# DevShield2_7_1.net
KiCad netlist of a schematic drawn in EAGLE
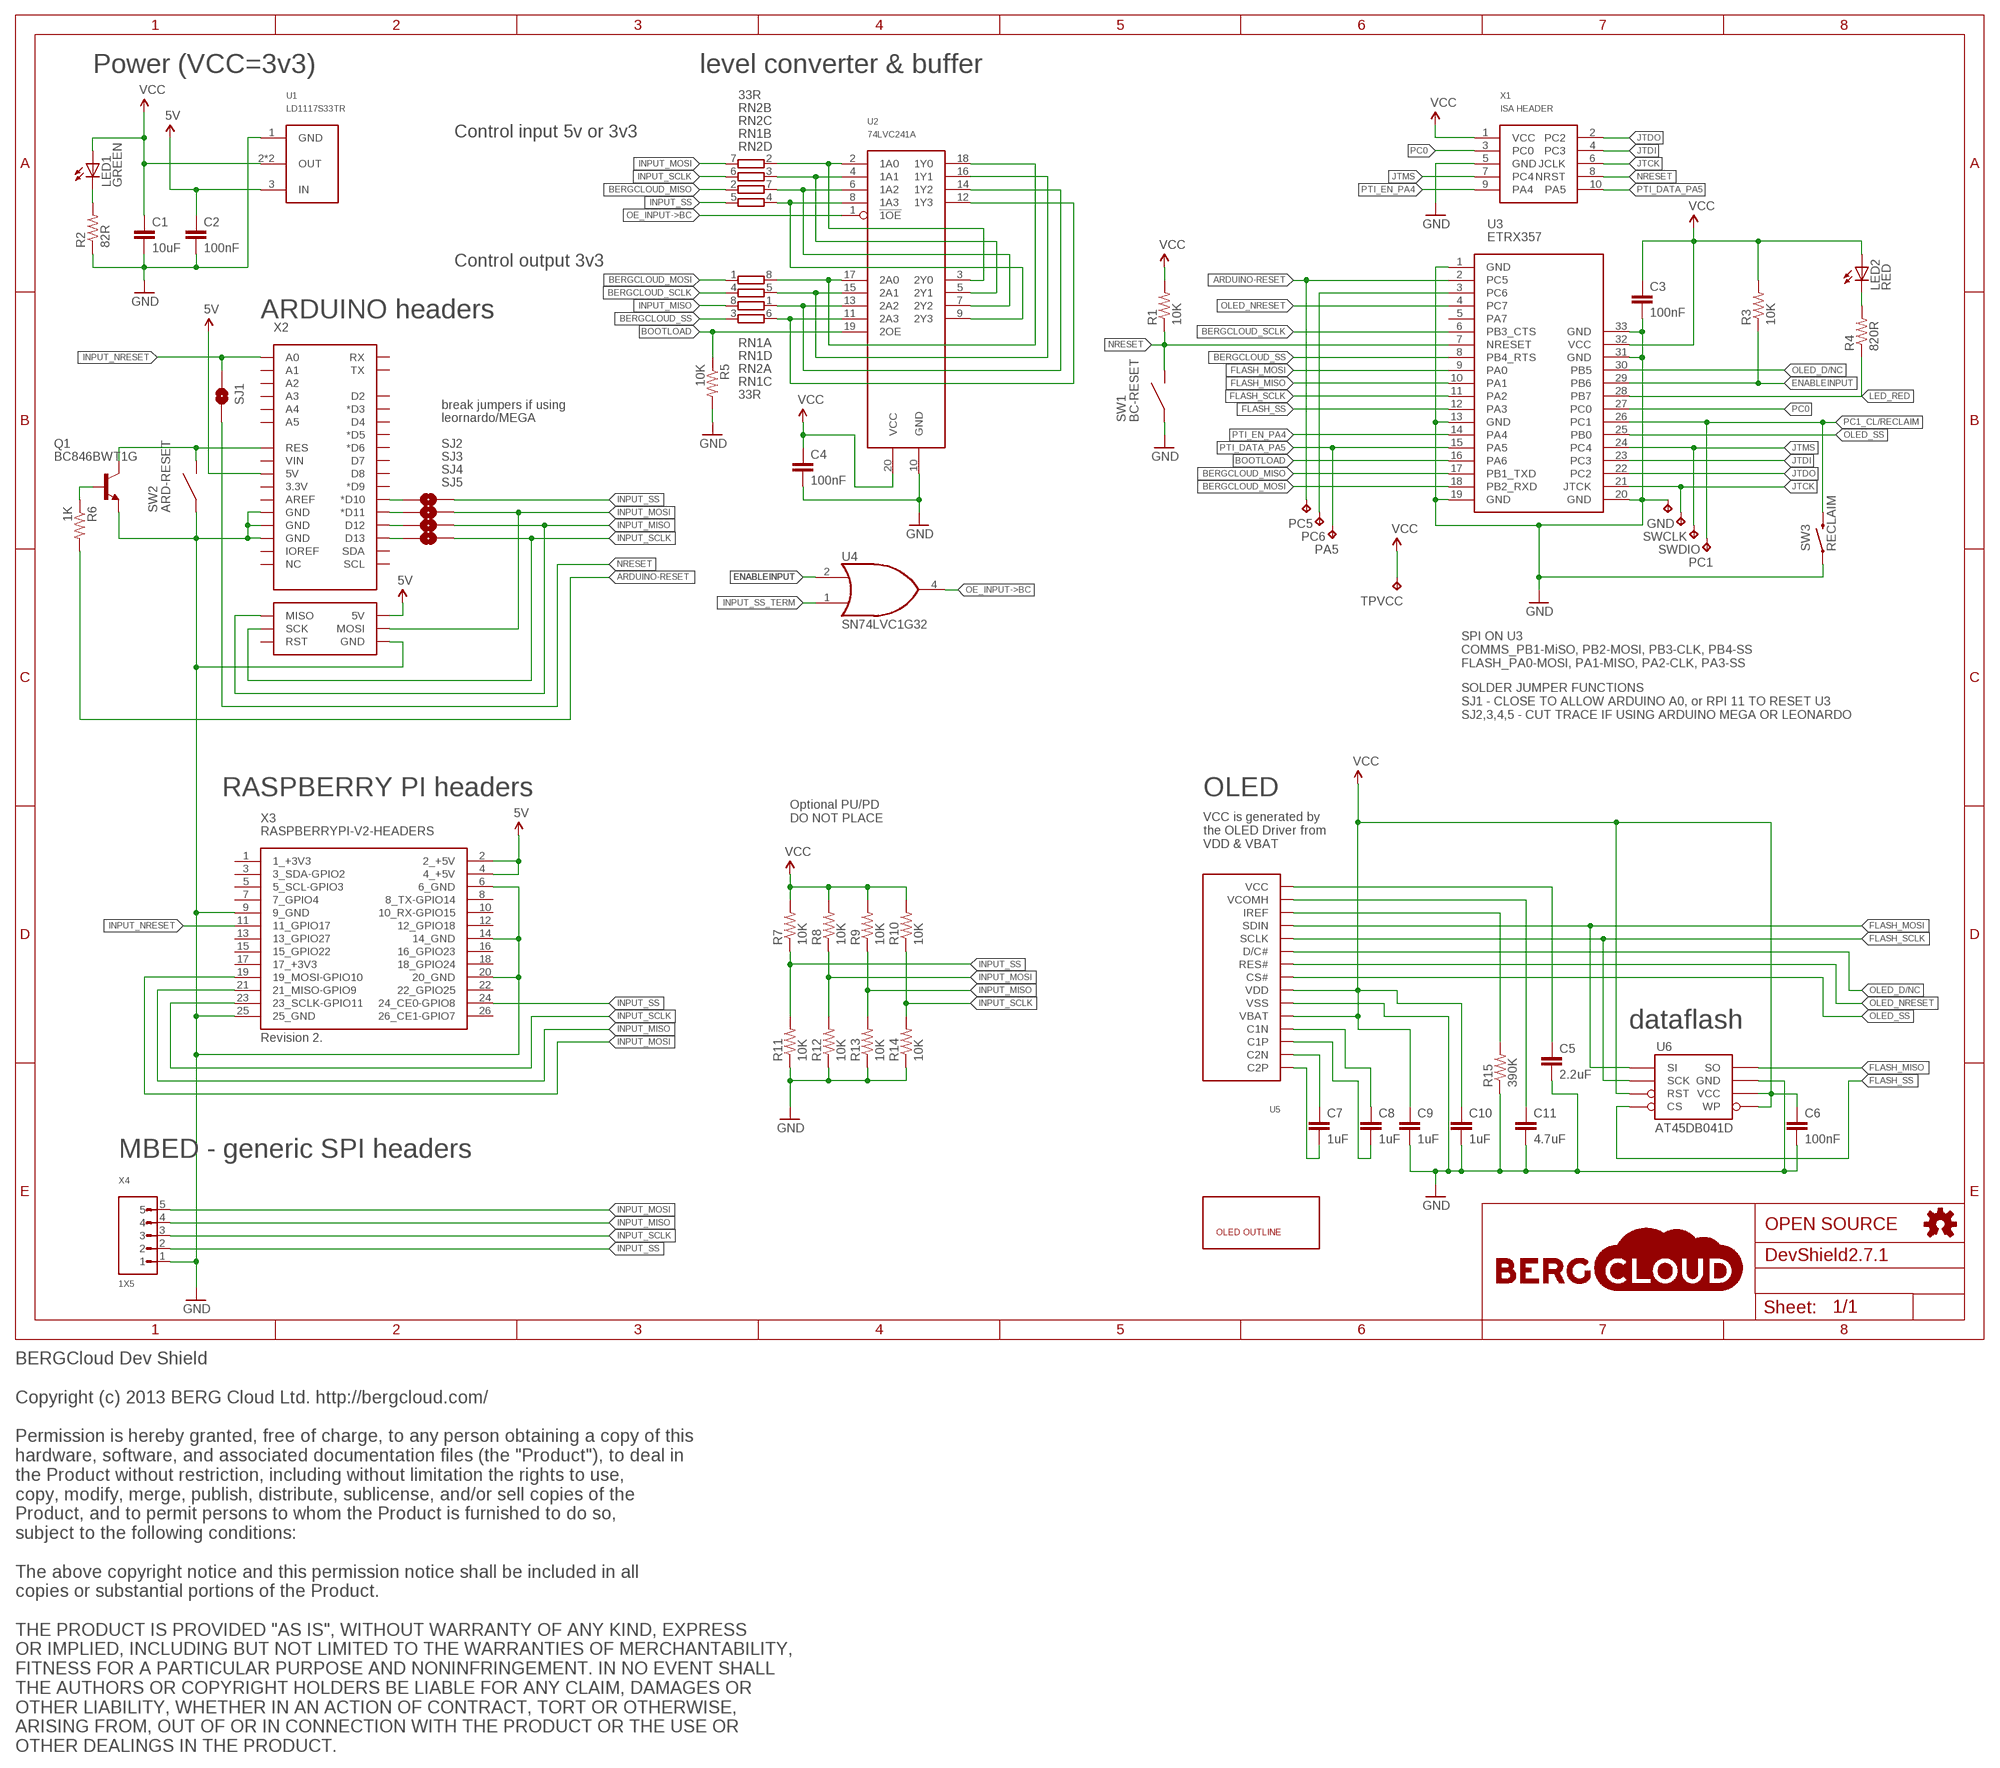
[diagram p0: schematic, sheet 1]

(export (version "E")
  (design (tool "Eeschema 10.0.6"))
  (components
    (comp (ref "C1")
      (value "10uF")
      (footprint "eagle-import:C0805K")
      (fields (field (name "MF") "AVX") (field (name "MPN") "06033C104KAZ2A"))
      (libsource (lib "eagle-import") (part "C-EUC0805K"))
    )
    (comp (ref "C2")
      (value "100nF")
      (footprint "eagle-import:C0603K")
      (fields (field (name "MF") "AVX") (field (name "MPN") "06033C104KAZ2A"))
      (libsource (lib "eagle-import") (part "C-EUC0603K"))
    )
    (comp (ref "C3")
      (value "100nF")
      (footprint "eagle-import:C0603K")
      (fields (field (name "MF") "AVX") (field (name "MPN") "06033C104KAZ2A"))
      (libsource (lib "eagle-import") (part "C-EUC0603K"))
    )
    (comp (ref "C4")
      (value "100nF")
      (footprint "eagle-import:C0603K")
      (fields (field (name "MF") "AVX") (field (name "MPN") "06033C104KAZ2A"))
      (libsource (lib "eagle-import") (part "C-EUC0603K"))
    )
    (comp (ref "C5")
      (value "2.2uF")
      (footprint "eagle-import:0603-CAP")
      (fields (field (name "MF") "AVX") (field (name "MPN") "06036D225KAT2A"))
      (libsource (lib "eagle-import") (part "CAP0603-CAP"))
    )
    (comp (ref "C6")
      (value "100nF")
      (footprint "eagle-import:C0603K")
      (fields (field (name "MF") "AVX") (field (name "MPN") "06033C104KAZ2A"))
      (libsource (lib "eagle-import") (part "C-EUC0603K"))
    )
    (comp (ref "C7")
      (value "1uF")
      (footprint "eagle-import:0603-CAP")
      (fields (field (name "MF") "AVX") (field (name "MPN") "02016D105MAT2A"))
      (libsource (lib "eagle-import") (part "CAP0603-CAP"))
    )
    (comp (ref "C8")
      (value "1uF")
      (footprint "eagle-import:0603-CAP")
      (fields (field (name "MF") "AVX") (field (name "MPN") "02016D105MAT2A"))
      (libsource (lib "eagle-import") (part "CAP0603-CAP"))
    )
    (comp (ref "C9")
      (value "1uF")
      (footprint "eagle-import:0603-CAP")
      (fields (field (name "MF") "AVX") (field (name "MPN") "02016D105MAT2A"))
      (libsource (lib "eagle-import") (part "CAP0603-CAP"))
    )
    (comp (ref "C10")
      (value "1uF")
      (footprint "eagle-import:0603-CAP")
      (fields (field (name "MF") "AVX") (field (name "MPN") "02016D105MAT2A"))
      (libsource (lib "eagle-import") (part "CAP0603-CAP"))
    )
    (comp (ref "C11")
      (value "4.7uF")
      (footprint "eagle-import:0805")
      (fields (field (name "MF") "AVX") (field (name "MPN") "0805ZD475KAT2A"))
      (libsource (lib "eagle-import") (part "CAP0805"))
    )
    (comp (ref "GND")
      (value "TPTP15R")
      (footprint "eagle-import:TP15R")
      (libsource (lib "eagle-import") (part "TPTP15R"))
    )
    (comp (ref "IGNORE")
      (value "ER-OLED0.91-1-OUTLINE")
      (footprint "eagle-import:ER-OLED0.91-SCREEN")
      (libsource (lib "eagle-import") (part "ER-OLED0.91-1-OUTLINE"))
    )
    (comp (ref "LED1")
      (value "GREEN")
      (footprint "eagle-import:CHIPLED_0603")
      (fields (field (name "MF") "AVAGO TECHNOLOGIES") (field (name "MPN") "ASMT-RH45-AQ502"))
      (libsource (lib "eagle-import") (part "LEDCHIPLED_0603"))
    )
    (comp (ref "LED2")
      (value "RED")
      (footprint "eagle-import:CHIPLED_0603")
      (fields (field (name "MF") "AVAGO TECHNOLOGIES") (field (name "MPN") "ASMT-RH45-AQ502"))
      (libsource (lib "eagle-import") (part "LEDCHIPLED_0603"))
    )
    (comp (ref "PA5")
      (value "TPTP15R")
      (footprint "eagle-import:TP15R")
      (libsource (lib "eagle-import") (part "TPTP15R"))
    )
    (comp (ref "PC1")
      (value "TPTP15R")
      (footprint "eagle-import:TP15R")
      (libsource (lib "eagle-import") (part "TPTP15R"))
    )
    (comp (ref "PC5")
      (value "TPTP15R")
      (footprint "eagle-import:TP15R")
      (libsource (lib "eagle-import") (part "TPTP15R"))
    )
    (comp (ref "PC6")
      (value "TPTP15R")
      (footprint "eagle-import:TP15R")
      (libsource (lib "eagle-import") (part "TPTP15R"))
    )
    (comp (ref "Q1")
      (value "BC846BWT1G")
      (footprint "eagle-import:SOT323")
      (fields
        (field (name "MF") "On Semi")
        (field (name "MF_1") "ON SEMICONDUCTOR")
        (field (name "MPN") "BC846BWT1G")
        (field (name "OC_FARNELL") "1653606")
      )
      (libsource (lib "eagle-import") (part "BC846BWT1G"))
    )
    (comp (ref "R1")
      (value "10K")
      (footprint "eagle-import:0603-RES")
      (libsource (lib "eagle-import") (part "RESISTOR0603-RES"))
    )
    (comp (ref "R2")
      (value "82R")
      (footprint "eagle-import:0603-RES")
      (libsource (lib "eagle-import") (part "RESISTOR0603-RES"))
    )
    (comp (ref "R3")
      (value "10K")
      (footprint "eagle-import:0603-RES")
      (libsource (lib "eagle-import") (part "RESISTOR0603-RES"))
    )
    (comp (ref "R4")
      (value "820R")
      (footprint "eagle-import:0603-RES")
      (libsource (lib "eagle-import") (part "RESISTOR0603-RES"))
    )
    (comp (ref "R5")
      (value "10K")
      (footprint "eagle-import:0603-RES")
      (libsource (lib "eagle-import") (part "RESISTOR0603-RES"))
    )
    (comp (ref "R6")
      (value "1K")
      (footprint "eagle-import:0603-RES")
      (fields (field (name "MF") "MULTICOMP") (field (name "MPN") "MC0063W060311K"))
      (libsource (lib "eagle-import") (part "RESISTOR0603-RES"))
    )
    (comp (ref "R7")
      (value "10K")
      (footprint "eagle-import:0603-RES")
      (libsource (lib "eagle-import") (part "RESISTOR0603-RES"))
    )
    (comp (ref "R8")
      (value "10K")
      (footprint "eagle-import:0603-RES")
      (libsource (lib "eagle-import") (part "RESISTOR0603-RES"))
    )
    (comp (ref "R9")
      (value "10K")
      (footprint "eagle-import:0603-RES")
      (libsource (lib "eagle-import") (part "RESISTOR0603-RES"))
    )
    (comp (ref "R10")
      (value "10K")
      (footprint "eagle-import:0603-RES")
      (libsource (lib "eagle-import") (part "RESISTOR0603-RES"))
    )
    (comp (ref "R11")
      (value "10K")
      (footprint "eagle-import:0603-RES")
      (libsource (lib "eagle-import") (part "RESISTOR0603-RES"))
    )
    (comp (ref "R12")
      (value "10K")
      (footprint "eagle-import:0603-RES")
      (libsource (lib "eagle-import") (part "RESISTOR0603-RES"))
    )
    (comp (ref "R13")
      (value "10K")
      (footprint "eagle-import:0603-RES")
      (libsource (lib "eagle-import") (part "RESISTOR0603-RES"))
    )
    (comp (ref "R14")
      (value "10K")
      (footprint "eagle-import:0603-RES")
      (libsource (lib "eagle-import") (part "RESISTOR0603-RES"))
    )
    (comp (ref "R15")
      (value "390K")
      (footprint "eagle-import:0603-RES")
      (fields (field (name "MF") "PANASONIC") (field (name "MPN") "ERJU03F3903V"))
      (libsource (lib "eagle-import") (part "RESISTOR0603-RES"))
    )
    (comp (ref "RN1")
      (value "33R")
      (footprint "eagle-import:CAT16")
      (fields (field (name "OC_FARNELL") "unknown"))
      (libsource (lib "eagle-import") (part "4R-NCAT16"))
    )
    (comp (ref "RN2")
      (value "33R")
      (footprint "eagle-import:CAT16")
      (fields (field (name "OC_FARNELL") "unknown"))
      (libsource (lib "eagle-import") (part "4R-NCAT16"))
    )
    (comp (ref "SJ1")
      (value "SOLDERJUMPERNO")
      (footprint "eagle-import:SJ_2S-NO")
      (libsource (lib "eagle-import") (part "SOLDERJUMPERNO"))
    )
    (comp (ref "SJ2")
      (value "SOLDERJUMPERTRACE")
      (footprint "eagle-import:SJ_2S-TRACE")
      (libsource (lib "eagle-import") (part "SOLDERJUMPERTRACE"))
    )
    (comp (ref "SJ3")
      (value "SOLDERJUMPERTRACE")
      (footprint "eagle-import:SJ_2S-TRACE")
      (libsource (lib "eagle-import") (part "SOLDERJUMPERTRACE"))
    )
    (comp (ref "SJ4")
      (value "SOLDERJUMPERTRACE")
      (footprint "eagle-import:SJ_2S-TRACE")
      (libsource (lib "eagle-import") (part "SOLDERJUMPERTRACE"))
    )
    (comp (ref "SJ5")
      (value "SOLDERJUMPERTRACE")
      (footprint "eagle-import:SJ_2S-TRACE")
      (libsource (lib "eagle-import") (part "SOLDERJUMPERTRACE"))
    )
    (comp (ref "SW1")
      (value "BC-RESET")
      (footprint "eagle-import:TE_FSMSM")
      (fields (field (name "MF") "TE CONNECTIVITY / ALCOSWITCH") (field (name "MPN") "FSMSM"))
      (libsource (lib "eagle-import") (part "SPST"))
    )
    (comp (ref "SW2")
      (value "ARD-RESET")
      (footprint "eagle-import:TE_FSMSM")
      (fields (field (name "MF") "TE CONNECTIVITY / ALCOSWITCH") (field (name "MPN") "FSMSM"))
      (libsource (lib "eagle-import") (part "SPST"))
    )
    (comp (ref "SW3")
      (value "RECLAIM")
      (footprint "eagle-import:TACTILE_SWITCH_SMD")
      (libsource (lib "eagle-import") (part "SWITCH-MOMENTARY-2SMD"))
    )
    (comp (ref "SWCLK")
      (value "TPTP15R")
      (footprint "eagle-import:TP15R")
      (libsource (lib "eagle-import") (part "TPTP15R"))
    )
    (comp (ref "SWDIO")
      (value "TPTP15R")
      (footprint "eagle-import:TP15R")
      (libsource (lib "eagle-import") (part "TPTP15R"))
    )
    (comp (ref "TPVCC")
      (value "TPTP15R")
      (footprint "eagle-import:TP15R")
      (libsource (lib "eagle-import") (part "TPTP15R"))
    )
    (comp (ref "U1")
      (value "LD1117S33TR")
      (footprint "eagle-import:SOT223")
      (libsource (lib "eagle-import") (part "LD1117S33TR"))
    )
    (comp (ref "U2")
      (value "74LVC241A")
      (footprint "eagle-import:TSSOP20")
      (libsource (lib "eagle-import") (part "74LVC241APW"))
    )
    (comp (ref "U3")
      (value "ETRX357")
      (footprint "eagle-import:ETRX35XSMD")
      (libsource (lib "eagle-import") (part "ETRX35XMODULE-SMD"))
    )
    (comp (ref "U4")
      (value "SN74LVC1G32")
      (footprint "eagle-import:SC70-5")
      (fields (field (name "MF") "TEXAS INSTRUMENTS") (field (name "MPN") "SN74LVC1G32DCKR"))
      (libsource (lib "eagle-import") (part "741G32LVC"))
    )
    (comp (ref "U5")
      (value "ER-OLED0.91-1HANDSOLDER_BOTTOMLAYER")
      (footprint "eagle-import:FPC15WAYOLED")
      (libsource (lib "eagle-import") (part "ER-OLED0.91-1HANDSOLDER_BOTTOMLAYER"))
    )
    (comp (ref "U6")
      (value "AT45DB041D")
      (footprint "eagle-import:SO08")
      (fields (field (name "MF") "ADESTO TECHNOLOGIES") (field (name "MPN") "AT45DB041D-SSU"))
      (libsource (lib "eagle-import") (part "AT45DB041B"))
    )
    (comp (ref "X1")
      (value "ISA HEADER")
      (footprint "eagle-import:SHF-105-01-L-D-SM")
      (libsource (lib "eagle-import") (part "EMBER_ISASHROUDED-1.27MM"))
    )
    (comp (ref "X2")
      (value "ARDUINO_UNO_IO_INCL_ICSP")
      (footprint "eagle-import:ARDUINO_UNO_ICSP")
      (libsource (lib "eagle-import") (part "ARDUINO_UNO_IO_INCL_ICSP"))
    )
    (comp (ref "X3")
      (value "RASPBERRYPI-V2-HEADERS")
      (footprint "eagle-import:13X2_2.54MM")
      (libsource (lib "eagle-import") (part "RASPBERRY-PIHEADERS"))
    )
    (comp (ref "X4")
      (value "1X5")
      (footprint "eagle-import:1X05")
      (libsource (lib "eagle-import") (part "1X5"))
    )
  )
  (nets
    (net (code "1") (name "5V") (class "Default")
      (node (ref "C2") (pin "1") (pinfunction "1_1") (pintype "passive"))
      (node (ref "U1") (pin "3") (pinfunction "IN_3") (pintype "bidirectional"))
      (node (ref "X2") (pin "5V@0") (pinfunction "5V_5V@0") (pintype "bidirectional"))
      (node (ref "X2") (pin "ICSP_5V") (pinfunction "5V_ICSP_5V") (pintype "bidirectional"))
      (node (ref "X3") (pin "2") (pinfunction "2_+5V_2") (pintype "bidirectional"))
      (node (ref "X3") (pin "4") (pinfunction "4_+5V_4") (pintype "bidirectional"))
    )
    (net (code "2") (name "ARDUINO-RESET") (class "Default")
      (node (ref "PC5") (pin "TP") (pinfunction "TP_TP") (pintype "input"))
      (node (ref "R6") (pin "2") (pinfunction "2_2") (pintype "passive"))
      (node (ref "U3") (pin "2") (pinfunction "PC5_2") (pintype "bidirectional"))
    )
    (net (code "3") (name "BERGCLOUD_MISO") (class "Default")
      (node (ref "RN1") (pin "2") (pinfunction "1_2") (pintype "passive"))
      (node (ref "U3") (pin "17") (pinfunction "PB1_TXD_17") (pintype "output"))
    )
    (net (code "4") (name "BERGCLOUD_MOSI") (class "Default")
      (node (ref "RN1") (pin "1") (pinfunction "1_1") (pintype "passive"))
      (node (ref "U3") (pin "18") (pinfunction "PB2_RXD_18") (pintype "input"))
    )
    (net (code "5") (name "BERGCLOUD_SCLK") (class "Default")
      (node (ref "RN1") (pin "4") (pinfunction "1_4") (pintype "passive"))
      (node (ref "U3") (pin "6") (pinfunction "PB3_CTS_6") (pintype "bidirectional"))
    )
    (net (code "6") (name "BERGCLOUD_SS") (class "Default")
      (node (ref "RN1") (pin "3") (pinfunction "1_3") (pintype "passive"))
      (node (ref "U3") (pin "8") (pinfunction "PB4_RTS_8") (pintype "bidirectional"))
    )
    (net (code "7") (name "BOOTLOAD") (class "Default")
      (node (ref "R5") (pin "1") (pinfunction "1_1") (pintype "passive"))
      (node (ref "U2") (pin "19") (pinfunction "2OE_19") (pintype "input"))
      (node (ref "U3") (pin "16") (pinfunction "PA6_16") (pintype "bidirectional"))
    )
    (net (code "8") (name "ENABLEINPUT") (class "Default")
      (node (ref "R3") (pin "1") (pinfunction "1_1") (pintype "passive"))
      (node (ref "U3") (pin "29") (pinfunction "PB6_29") (pintype "bidirectional"))
      (node (ref "U4") (pin "2") (pinfunction "I0_2") (pintype "input"))
    )
    (net (code "9") (name "FLASH_MISO") (class "Default")
      (node (ref "U3") (pin "10") (pinfunction "PA1_10") (pintype "bidirectional"))
      (node (ref "U6") (pin "8") (pinfunction "SO_8") (pintype "bidirectional"))
    )
    (net (code "10") (name "FLASH_MOSI") (class "Default")
      (node (ref "U3") (pin "9") (pinfunction "PA0_9") (pintype "bidirectional"))
      (node (ref "U5") (pin "P$12") (pinfunction "SDIN_P$12") (pintype "bidirectional"))
      (node (ref "U6") (pin "1") (pinfunction "SI_1") (pintype "bidirectional"))
    )
    (net (code "11") (name "FLASH_SCLK") (class "Default")
      (node (ref "U3") (pin "11") (pinfunction "PA2_11") (pintype "bidirectional"))
      (node (ref "U5") (pin "P$11") (pinfunction "SCLK_P$11") (pintype "bidirectional"))
      (node (ref "U6") (pin "2") (pinfunction "SCK_2") (pintype "bidirectional"))
    )
    (net (code "12") (name "FLASH_SS") (class "Default")
      (node (ref "U3") (pin "12") (pinfunction "PA3_12") (pintype "bidirectional"))
      (node (ref "U6") (pin "4") (pinfunction "CS_4") (pintype "bidirectional"))
    )
    (net (code "13") (name "GND") (class "Default")
      (node (ref "C1") (pin "2") (pinfunction "2_2") (pintype "passive"))
      (node (ref "C10") (pin "2") (pinfunction "2_2") (pintype "passive"))
      (node (ref "C11") (pin "2") (pinfunction "2_2") (pintype "passive"))
      (node (ref "C2") (pin "2") (pinfunction "2_2") (pintype "passive"))
      (node (ref "C3") (pin "2") (pinfunction "2_2") (pintype "passive"))
      (node (ref "C4") (pin "2") (pinfunction "2_2") (pintype "passive"))
      (node (ref "C5") (pin "2") (pinfunction "2_2") (pintype "passive"))
      (node (ref "C6") (pin "2") (pinfunction "2_2") (pintype "passive"))
      (node (ref "C9") (pin "2") (pinfunction "2_2") (pintype "passive"))
      (node (ref "GND") (pin "TP") (pinfunction "TP_TP") (pintype "input"))
      (node (ref "Q1") (pin "2") (pinfunction "E_2") (pintype "passive"))
      (node (ref "R11") (pin "1") (pinfunction "1_1") (pintype "passive"))
      (node (ref "R12") (pin "1") (pinfunction "1_1") (pintype "passive"))
      (node (ref "R13") (pin "1") (pinfunction "1_1") (pintype "passive"))
      (node (ref "R14") (pin "1") (pinfunction "1_1") (pintype "passive"))
      (node (ref "R15") (pin "1") (pinfunction "1_1") (pintype "passive"))
      (node (ref "R2") (pin "1") (pinfunction "1_1") (pintype "passive"))
      (node (ref "R5") (pin "2") (pinfunction "2_2") (pintype "passive"))
      (node (ref "SW1") (pin "P$2") (pinfunction "P$2_P$2") (pintype "bidirectional"))
      (node (ref "SW2") (pin "P$2") (pinfunction "P$2_P$2") (pintype "bidirectional"))
      (node (ref "SW3") (pin "1") (pinfunction "1_1") (pintype "passive"))
      (node (ref "U1") (pin "1") (pinfunction "GND_1") (pintype "bidirectional"))
      (node (ref "U2") (pin "10") (pinfunction "GND_10") (pintype "bidirectional"))
      (node (ref "U3") (pin "1") (pinfunction "GND_1") (pintype "power_in"))
      (node (ref "U3") (pin "13") (pinfunction "GND_13") (pintype "power_in"))
      (node (ref "U3") (pin "19") (pinfunction "GND_19") (pintype "power_in"))
      (node (ref "U3") (pin "20") (pinfunction "GND_20") (pintype "power_in"))
      (node (ref "U3") (pin "31") (pinfunction "GND_31") (pintype "power_in"))
      (node (ref "U3") (pin "33") (pinfunction "GND_33") (pintype "power_in"))
      (node (ref "U5") (pin "P$6") (pinfunction "VSS_P$6") (pintype "bidirectional"))
      (node (ref "U6") (pin "7") (pinfunction "GND_7") (pintype "bidirectional"))
      (node (ref "X1") (pin "5") (pinfunction "GND_5") (pintype "bidirectional"))
      (node (ref "X2") (pin "GND@0") (pinfunction "GND_GND@0") (pintype "bidirectional"))
      (node (ref "X2") (pin "GND@03") (pinfunction "GND_GND@03") (pintype "bidirectional"))
      (node (ref "X2") (pin "GND@1") (pinfunction "GND_GND@1") (pintype "bidirectional"))
      (node (ref "X2") (pin "GND@2") (pinfunction "GND_GND@2") (pintype "bidirectional"))
      (node (ref "X3") (pin "14") (pinfunction "14_GND_14") (pintype "bidirectional"))
      (node (ref "X3") (pin "20") (pinfunction "20_GND_20") (pintype "bidirectional"))
      (node (ref "X3") (pin "25") (pinfunction "25_GND_25") (pintype "bidirectional"))
      (node (ref "X3") (pin "6") (pinfunction "6_GND_6") (pintype "bidirectional"))
      (node (ref "X3") (pin "9") (pinfunction "9_GND_9") (pintype "bidirectional"))
      (node (ref "X4") (pin "1") (pinfunction "1_1") (pintype "bidirectional"))
    )
    (net (code "14") (name "INPUT_MISO") (class "Default")
      (node (ref "R13") (pin "2") (pinfunction "2_2") (pintype "passive"))
      (node (ref "R9") (pin "1") (pinfunction "1_1") (pintype "passive"))
      (node (ref "RN2") (pin "8") (pinfunction "2_8") (pintype "passive"))
      (node (ref "SJ4") (pin "2") (pinfunction "2_2") (pintype "passive"))
      (node (ref "X2") (pin "ICSP_MISO") (pinfunction "MISO_ICSP_MISO") (pintype "bidirectional"))
      (node (ref "X3") (pin "21") (pinfunction "21_MISO-GPIO9_21") (pintype "bidirectional"))
      (node (ref "X4") (pin "4") (pinfunction "4_4") (pintype "bidirectional"))
    )
    (net (code "15") (name "INPUT_MOSI") (class "Default")
      (node (ref "R12") (pin "2") (pinfunction "2_2") (pintype "passive"))
      (node (ref "R8") (pin "1") (pinfunction "1_1") (pintype "passive"))
      (node (ref "RN2") (pin "7") (pinfunction "2_7") (pintype "passive"))
      (node (ref "SJ3") (pin "2") (pinfunction "2_2") (pintype "passive"))
      (node (ref "X2") (pin "ICSP_MOSI") (pinfunction "MOSI_ICSP_MOSI") (pintype "bidirectional"))
      (node (ref "X3") (pin "19") (pinfunction "19_MOSI-GPIO10_19") (pintype "bidirectional"))
      (node (ref "X4") (pin "5") (pinfunction "5_5") (pintype "bidirectional"))
    )
    (net (code "16") (name "INPUT_NRESET") (class "Default")
      (node (ref "SJ1") (pin "1") (pinfunction "1_1") (pintype "passive"))
      (node (ref "X2") (pin "A0") (pinfunction "A0_A0") (pintype "bidirectional"))
      (node (ref "X3") (pin "11") (pinfunction "11_GPIO17_11") (pintype "bidirectional"))
    )
    (net (code "17") (name "INPUT_SCLK") (class "Default")
      (node (ref "R10") (pin "1") (pinfunction "1_1") (pintype "passive"))
      (node (ref "R14") (pin "2") (pinfunction "2_2") (pintype "passive"))
      (node (ref "RN2") (pin "6") (pinfunction "2_6") (pintype "passive"))
      (node (ref "SJ5") (pin "2") (pinfunction "2_2") (pintype "passive"))
      (node (ref "X2") (pin "ICSP_SCK") (pinfunction "SCK_ICSP_SCK") (pintype "bidirectional"))
      (node (ref "X3") (pin "23") (pinfunction "23_SCLK-GPIO11_23") (pintype "bidirectional"))
      (node (ref "X4") (pin "3") (pinfunction "3_3") (pintype "bidirectional"))
    )
    (net (code "18") (name "INPUT_SS") (class "Default")
      (node (ref "R11") (pin "2") (pinfunction "2_2") (pintype "passive"))
      (node (ref "R7") (pin "1") (pinfunction "1_1") (pintype "passive"))
      (node (ref "RN2") (pin "5") (pinfunction "2_5") (pintype "passive"))
      (node (ref "SJ2") (pin "2") (pinfunction "2_2") (pintype "passive"))
      (node (ref "X3") (pin "24") (pinfunction "24_CE0-GPIO8_24") (pintype "bidirectional"))
      (node (ref "X4") (pin "2") (pinfunction "2_2") (pintype "bidirectional"))
    )
    (net (code "19") (name "INPUT_SS_TERM") (class "Default")
      (node (ref "RN2") (pin "4") (pinfunction "1_4") (pintype "passive"))
      (node (ref "U2") (pin "8") (pinfunction "1A3_8") (pintype "bidirectional"))
      (node (ref "U2") (pin "9") (pinfunction "2Y3_9") (pintype "bidirectional"))
      (node (ref "U4") (pin "1") (pinfunction "I1_1") (pintype "input"))
    )
    (net (code "20") (name "JTCK") (class "Default")
      (node (ref "SWCLK") (pin "TP") (pinfunction "TP_TP") (pintype "input"))
      (node (ref "U3") (pin "21") (pinfunction "JTCK_21") (pintype "bidirectional"))
      (node (ref "X1") (pin "6") (pinfunction "JCLK_6") (pintype "bidirectional"))
    )
    (net (code "21") (name "JTDI") (class "Default")
      (node (ref "U3") (pin "23") (pinfunction "PC3_23") (pintype "bidirectional"))
      (node (ref "X1") (pin "4") (pinfunction "PC3_4") (pintype "bidirectional"))
    )
    (net (code "22") (name "JTDO") (class "Default")
      (node (ref "U3") (pin "22") (pinfunction "PC2_22") (pintype "bidirectional"))
      (node (ref "X1") (pin "2") (pinfunction "PC2_2") (pintype "bidirectional"))
    )
    (net (code "23") (name "JTMS") (class "Default")
      (node (ref "SWDIO") (pin "TP") (pinfunction "TP_TP") (pintype "input"))
      (node (ref "U3") (pin "24") (pinfunction "PC4_24") (pintype "bidirectional"))
      (node (ref "X1") (pin "7") (pinfunction "PC4_7") (pintype "bidirectional"))
    )
    (net (code "24") (name "LED_RED") (class "Default")
      (node (ref "R4") (pin "1") (pinfunction "1_1") (pintype "passive"))
      (node (ref "U3") (pin "28") (pinfunction "PB7_28") (pintype "bidirectional"))
    )
    (net (code "25") (name "NRESET") (class "Default")
      (node (ref "R1") (pin "1") (pinfunction "1_1") (pintype "passive"))
      (node (ref "SJ1") (pin "2") (pinfunction "2_2") (pintype "passive"))
      (node (ref "SW1") (pin "P$1") (pinfunction "P$1_P$1") (pintype "bidirectional"))
      (node (ref "U3") (pin "7") (pinfunction "NRESET_7") (pintype "bidirectional"))
      (node (ref "X1") (pin "8") (pinfunction "NRST_8") (pintype "bidirectional"))
    )
    (net (code "26") (name "Net-(LED1-PadC)") (class "Default")
      (node (ref "LED1") (pin "C") (pinfunction "C_C") (pintype "passive"))
      (node (ref "R2") (pin "2") (pinfunction "2_2") (pintype "passive"))
    )
    (net (code "27") (name "Net-(LED2-PadC)") (class "Default")
      (node (ref "LED2") (pin "C") (pinfunction "C_C") (pintype "passive"))
      (node (ref "R4") (pin "2") (pinfunction "2_2") (pintype "passive"))
    )
    (net (code "28") (name "Net-(Q1-B)") (class "Default")
      (node (ref "Q1") (pin "1") (pinfunction "B_1") (pintype "passive"))
      (node (ref "R6") (pin "1") (pinfunction "1_1") (pintype "passive"))
    )
    (net (code "29") (name "Net-(Q1-C)") (class "Default")
      (node (ref "Q1") (pin "3") (pinfunction "C_3") (pintype "passive"))
      (node (ref "SW2") (pin "P$1") (pinfunction "P$1_P$1") (pintype "bidirectional"))
      (node (ref "X2") (pin "RES") (pinfunction "RES_RES") (pintype "bidirectional"))
    )
    (net (code "30") (name "Net-(RN1A-2)") (class "Default")
      (node (ref "RN1") (pin "8") (pinfunction "2_8") (pintype "passive"))
      (node (ref "U2") (pin "17") (pinfunction "2A0_17") (pintype "bidirectional"))
      (node (ref "U2") (pin "18") (pinfunction "1Y0_18") (pintype "bidirectional"))
    )
    (net (code "31") (name "Net-(RN1B-2)") (class "Default")
      (node (ref "RN1") (pin "7") (pinfunction "2_7") (pintype "passive"))
      (node (ref "U2") (pin "6") (pinfunction "1A2_6") (pintype "bidirectional"))
      (node (ref "U2") (pin "7") (pinfunction "2Y2_7") (pintype "bidirectional"))
    )
    (net (code "32") (name "Net-(RN1C-2)") (class "Default")
      (node (ref "RN1") (pin "6") (pinfunction "2_6") (pintype "passive"))
      (node (ref "U2") (pin "11") (pinfunction "2A3_11") (pintype "bidirectional"))
      (node (ref "U2") (pin "12") (pinfunction "1Y3_12") (pintype "bidirectional"))
    )
    (net (code "33") (name "Net-(RN1D-2)") (class "Default")
      (node (ref "RN1") (pin "5") (pinfunction "2_5") (pintype "passive"))
      (node (ref "U2") (pin "15") (pinfunction "2A1_15") (pintype "bidirectional"))
      (node (ref "U2") (pin "16") (pinfunction "1Y1_16") (pintype "bidirectional"))
    )
    (net (code "34") (name "Net-(RN2B-1)") (class "Default")
      (node (ref "RN2") (pin "2") (pinfunction "1_2") (pintype "passive"))
      (node (ref "U2") (pin "2") (pinfunction "1A0_2") (pintype "bidirectional"))
      (node (ref "U2") (pin "3") (pinfunction "2Y0_3") (pintype "bidirectional"))
    )
    (net (code "35") (name "Net-(RN2C-1)") (class "Default")
      (node (ref "RN2") (pin "3") (pinfunction "1_3") (pintype "passive"))
      (node (ref "U2") (pin "4") (pinfunction "1A1_4") (pintype "bidirectional"))
      (node (ref "U2") (pin "5") (pinfunction "2Y1_5") (pintype "bidirectional"))
    )
    (net (code "36") (name "Net-(SJ4-Pad1)") (class "Default")
      (node (ref "SJ4") (pin "1") (pinfunction "1_1") (pintype "passive"))
      (node (ref "X2") (pin "D12") (pinfunction "D12_D12") (pintype "bidirectional"))
    )
    (net (code "37") (name "Net-(SJ5-Pad1)") (class "Default")
      (node (ref "SJ5") (pin "1") (pinfunction "1_1") (pintype "passive"))
      (node (ref "X2") (pin "D13") (pinfunction "D13_D13") (pintype "bidirectional"))
    )
    (net (code "38") (name "Net-(U2-1Y2)") (class "Default")
      (node (ref "RN2") (pin "1") (pinfunction "1_1") (pintype "passive"))
      (node (ref "U2") (pin "13") (pinfunction "2A2_13") (pintype "bidirectional"))
      (node (ref "U2") (pin "14") (pinfunction "1Y2_14") (pintype "bidirectional"))
    )
    (net (code "39") (name "Net-(U3-PC6)") (class "Default")
      (node (ref "PC6") (pin "TP") (pinfunction "TP_TP") (pintype "input"))
      (node (ref "U3") (pin "3") (pinfunction "PC6_3") (pintype "bidirectional"))
    )
    (net (code "40") (name "Net-(U5-C1N)") (class "Default")
      (node (ref "C8") (pin "1") (pinfunction "1_1") (pintype "passive"))
      (node (ref "U5") (pin "P$4") (pinfunction "C1N_P$4") (pintype "bidirectional"))
    )
    (net (code "41") (name "Net-(U5-C1P)") (class "Default")
      (node (ref "C8") (pin "2") (pinfunction "2_2") (pintype "passive"))
      (node (ref "U5") (pin "P$3") (pinfunction "C1P_P$3") (pintype "bidirectional"))
    )
    (net (code "42") (name "Net-(U5-C2N)") (class "Default")
      (node (ref "C7") (pin "1") (pinfunction "1_1") (pintype "passive"))
      (node (ref "U5") (pin "P$2") (pinfunction "C2N_P$2") (pintype "bidirectional"))
    )
    (net (code "43") (name "Net-(U5-C2P)") (class "Default")
      (node (ref "C7") (pin "2") (pinfunction "2_2") (pintype "passive"))
      (node (ref "U5") (pin "P$1") (pinfunction "C2P_P$1") (pintype "bidirectional"))
    )
    (net (code "44") (name "Net-(U5-IREF)") (class "Default")
      (node (ref "R15") (pin "2") (pinfunction "2_2") (pintype "passive"))
      (node (ref "U5") (pin "P$13") (pinfunction "IREF_P$13") (pintype "bidirectional"))
    )
    (net (code "45") (name "Net-(U5-VCC)") (class "Default")
      (node (ref "C5") (pin "1") (pinfunction "1_1") (pintype "passive"))
      (node (ref "U5") (pin "P$15") (pinfunction "VCC_P$15") (pintype "bidirectional"))
    )
    (net (code "46") (name "Net-(U5-VCOMH)") (class "Default")
      (node (ref "C11") (pin "1") (pinfunction "1_1") (pintype "passive"))
      (node (ref "U5") (pin "P$14") (pinfunction "VCOMH_P$14") (pintype "bidirectional"))
    )
    (net (code "47") (name "Net-(X2-*D10)") (class "Default")
      (node (ref "SJ2") (pin "1") (pinfunction "1_1") (pintype "passive"))
      (node (ref "X2") (pin "D10") (pinfunction "*D10_D10") (pintype "bidirectional"))
    )
    (net (code "48") (name "Net-(X2-*D11)") (class "Default")
      (node (ref "SJ3") (pin "1") (pinfunction "1_1") (pintype "passive"))
      (node (ref "X2") (pin "D11") (pinfunction "*D11_D11") (pintype "bidirectional"))
    )
    (net (code "49") (name "OE_INPUT->BC") (class "Default")
      (node (ref "U2") (pin "1") (pinfunction "~{1OE}_1") (pintype "input"))
      (node (ref "U4") (pin "4") (pinfunction "O_4") (pintype "output"))
    )
    (net (code "50") (name "OLED_D{slash}NC") (class "Default")
      (node (ref "U3") (pin "30") (pinfunction "PB5_30") (pintype "bidirectional"))
      (node (ref "U5") (pin "P$10") (pinfunction "D/C#_P$10") (pintype "bidirectional"))
    )
    (net (code "51") (name "OLED_NRESET") (class "Default")
      (node (ref "U3") (pin "4") (pinfunction "PC7_4") (pintype "bidirectional"))
      (node (ref "U5") (pin "P$9") (pinfunction "RES#_P$9") (pintype "bidirectional"))
    )
    (net (code "52") (name "OLED_SS") (class "Default")
      (node (ref "U3") (pin "25") (pinfunction "PB0_25") (pintype "bidirectional"))
      (node (ref "U5") (pin "P$8") (pinfunction "CS#_P$8") (pintype "bidirectional"))
    )
    (net (code "53") (name "PC0") (class "Default")
      (node (ref "U3") (pin "27") (pinfunction "PC0_27") (pintype "bidirectional"))
      (node (ref "X1") (pin "3") (pinfunction "PC0_3") (pintype "bidirectional"))
    )
    (net (code "54") (name "PC1_CL{slash}RECLAIM") (class "Default")
      (node (ref "PC1") (pin "TP") (pinfunction "TP_TP") (pintype "input"))
      (node (ref "SW3") (pin "3") (pinfunction "2_3") (pintype "passive"))
      (node (ref "U3") (pin "26") (pinfunction "PC1_26") (pintype "bidirectional"))
    )
    (net (code "55") (name "PTI_DATA_PA5") (class "Default")
      (node (ref "PA5") (pin "TP") (pinfunction "TP_TP") (pintype "input"))
      (node (ref "U3") (pin "15") (pinfunction "PA5_15") (pintype "bidirectional"))
      (node (ref "X1") (pin "10") (pinfunction "PA5_10") (pintype "bidirectional"))
    )
    (net (code "56") (name "PTI_EN_PA4") (class "Default")
      (node (ref "U3") (pin "14") (pinfunction "PA4_14") (pintype "bidirectional"))
      (node (ref "X1") (pin "9") (pinfunction "PA4_9") (pintype "bidirectional"))
    )
    (net (code "57") (name "VCC") (class "Default")
      (node (ref "C1") (pin "1") (pinfunction "1_1") (pintype "passive"))
      (node (ref "C10") (pin "1") (pinfunction "1_1") (pintype "passive"))
      (node (ref "C3") (pin "1") (pinfunction "1_1") (pintype "passive"))
      (node (ref "C4") (pin "1") (pinfunction "1_1") (pintype "passive"))
      (node (ref "C6") (pin "1") (pinfunction "1_1") (pintype "passive"))
      (node (ref "C9") (pin "1") (pinfunction "1_1") (pintype "passive"))
      (node (ref "LED1") (pin "A") (pinfunction "A_A") (pintype "passive"))
      (node (ref "LED2") (pin "A") (pinfunction "A_A") (pintype "passive"))
      (node (ref "R1") (pin "2") (pinfunction "2_2") (pintype "passive"))
      (node (ref "R10") (pin "2") (pinfunction "2_2") (pintype "passive"))
      (node (ref "R3") (pin "2") (pinfunction "2_2") (pintype "passive"))
      (node (ref "R7") (pin "2") (pinfunction "2_2") (pintype "passive"))
      (node (ref "R8") (pin "2") (pinfunction "2_2") (pintype "passive"))
      (node (ref "R9") (pin "2") (pinfunction "2_2") (pintype "passive"))
      (node (ref "TPVCC") (pin "TP") (pinfunction "TP_TP") (pintype "input"))
      (node (ref "U1") (pin "2") (pinfunction "OUT_2") (pintype "bidirectional"))
      (node (ref "U1") (pin "4") (pinfunction "OUT_4") (pintype "bidirectional"))
      (node (ref "U2") (pin "20") (pinfunction "VCC_20") (pintype "bidirectional"))
      (node (ref "U3") (pin "32") (pinfunction "VCC_32") (pintype "power_in"))
      (node (ref "U5") (pin "P$5") (pinfunction "VBAT_P$5") (pintype "bidirectional"))
      (node (ref "U5") (pin "P$7") (pinfunction "VDD_P$7") (pintype "bidirectional"))
      (node (ref "U6") (pin "3") (pinfunction "RST_3") (pintype "bidirectional"))
      (node (ref "U6") (pin "5") (pinfunction "WP_5") (pintype "bidirectional"))
      (node (ref "U6") (pin "6") (pinfunction "VCC_6") (pintype "bidirectional"))
      (node (ref "X1") (pin "1") (pinfunction "VCC_1") (pintype "bidirectional"))
    )
    (net (code "58") (name "unconnected-(U3-PA7-Pad5)") (class "Default")
      (node (ref "U3") (pin "5") (pinfunction "PA7_5") (pintype "bidirectional"))
    )
    (net (code "59") (name "unconnected-(X2-*D3-PadD3)") (class "Default")
      (node (ref "X2") (pin "D3") (pinfunction "*D3_D3") (pintype "bidirectional"))
    )
    (net (code "60") (name "unconnected-(X2-*D5-PadD5)") (class "Default")
      (node (ref "X2") (pin "D5") (pinfunction "*D5_D5") (pintype "bidirectional"))
    )
    (net (code "61") (name "unconnected-(X2-*D6-PadD6)") (class "Default")
      (node (ref "X2") (pin "D6") (pinfunction "*D6_D6") (pintype "bidirectional"))
    )
    (net (code "62") (name "unconnected-(X2-*D9-PadD9)") (class "Default")
      (node (ref "X2") (pin "D9") (pinfunction "*D9_D9") (pintype "bidirectional"))
    )
    (net (code "63") (name "unconnected-(X2-Pad3.3V)") (class "Default")
      (node (ref "X2") (pin "3.3V") (pinfunction "3.3V_3.3V") (pintype "bidirectional"))
    )
    (net (code "64") (name "unconnected-(X2-PadA1)") (class "Default")
      (node (ref "X2") (pin "A1") (pinfunction "A1_A1") (pintype "bidirectional"))
    )
    (net (code "65") (name "unconnected-(X2-PadA2)") (class "Default")
      (node (ref "X2") (pin "A2") (pinfunction "A2_A2") (pintype "bidirectional"))
    )
    (net (code "66") (name "unconnected-(X2-PadA3)") (class "Default")
      (node (ref "X2") (pin "A3") (pinfunction "A3_A3") (pintype "bidirectional"))
    )
    (net (code "67") (name "unconnected-(X2-PadA4)") (class "Default")
      (node (ref "X2") (pin "A4") (pinfunction "A4_A4") (pintype "bidirectional"))
    )
    (net (code "68") (name "unconnected-(X2-PadA5)") (class "Default")
      (node (ref "X2") (pin "A5") (pinfunction "A5_A5") (pintype "bidirectional"))
    )
    (net (code "69") (name "unconnected-(X2-PadAREF)") (class "Default")
      (node (ref "X2") (pin "AREF") (pinfunction "AREF_AREF") (pintype "bidirectional"))
    )
    (net (code "70") (name "unconnected-(X2-PadD2)") (class "Default")
      (node (ref "X2") (pin "D2") (pinfunction "D2_D2") (pintype "bidirectional"))
    )
    (net (code "71") (name "unconnected-(X2-PadD4)") (class "Default")
      (node (ref "X2") (pin "D4") (pinfunction "D4_D4") (pintype "bidirectional"))
    )
    (net (code "72") (name "unconnected-(X2-PadD7)") (class "Default")
      (node (ref "X2") (pin "D7") (pinfunction "D7_D7") (pintype "bidirectional"))
    )
    (net (code "73") (name "unconnected-(X2-PadD8)") (class "Default")
      (node (ref "X2") (pin "D8") (pinfunction "D8_D8") (pintype "bidirectional"))
    )
    (net (code "74") (name "unconnected-(X2-PadIOREF)") (class "Default")
      (node (ref "X2") (pin "IOREF") (pinfunction "IOREF_IOREF") (pintype "bidirectional"))
    )
    (net (code "75") (name "unconnected-(X2-PadNC)") (class "Default")
      (node (ref "X2") (pin "NC") (pinfunction "NC_NC") (pintype "bidirectional"))
    )
    (net (code "76") (name "unconnected-(X2-PadRX)") (class "Default")
      (node (ref "X2") (pin "RX") (pinfunction "RX_RX") (pintype "bidirectional"))
    )
    (net (code "77") (name "unconnected-(X2-PadSCL)") (class "Default")
      (node (ref "X2") (pin "SCL") (pinfunction "SCL_SCL") (pintype "bidirectional"))
    )
    (net (code "78") (name "unconnected-(X2-PadSDA)") (class "Default")
      (node (ref "X2") (pin "SDA") (pinfunction "SDA_SDA") (pintype "bidirectional"))
    )
    (net (code "79") (name "unconnected-(X2-PadTX)") (class "Default")
      (node (ref "X2") (pin "TX") (pinfunction "TX_TX") (pintype "bidirectional"))
    )
    (net (code "80") (name "unconnected-(X2-PadVIN)") (class "Default")
      (node (ref "X2") (pin "VIN") (pinfunction "VIN_VIN") (pintype "bidirectional"))
    )
    (net (code "81") (name "unconnected-(X2-RST-PadICSP_RST)") (class "Default")
      (node (ref "X2") (pin "ICSP_RST") (pinfunction "RST_ICSP_RST") (pintype "bidirectional"))
    )
    (net (code "82") (name "unconnected-(X3-1_+3V3-Pad1)") (class "Default")
      (node (ref "X3") (pin "1") (pinfunction "1_+3V3_1") (pintype "bidirectional"))
    )
    (net (code "83") (name "unconnected-(X3-3_SDA-GPIO2-Pad3)") (class "Default")
      (node (ref "X3") (pin "3") (pinfunction "3_SDA-GPIO2_3") (pintype "bidirectional"))
    )
    (net (code "84") (name "unconnected-(X3-5_SCL-GPIO3-Pad5)") (class "Default")
      (node (ref "X3") (pin "5") (pinfunction "5_SCL-GPIO3_5") (pintype "bidirectional"))
    )
    (net (code "85") (name "unconnected-(X3-7_GPIO4-Pad7)") (class "Default")
      (node (ref "X3") (pin "7") (pinfunction "7_GPIO4_7") (pintype "bidirectional"))
    )
    (net (code "86") (name "unconnected-(X3-8_TX-GPIO14-Pad8)") (class "Default")
      (node (ref "X3") (pin "8") (pinfunction "8_TX-GPIO14_8") (pintype "bidirectional"))
    )
    (net (code "87") (name "unconnected-(X3-10_RX-GPIO15-Pad10)") (class "Default")
      (node (ref "X3") (pin "10") (pinfunction "10_RX-GPIO15_10") (pintype "bidirectional"))
    )
    (net (code "88") (name "unconnected-(X3-12_GPIO18-Pad12)") (class "Default")
      (node (ref "X3") (pin "12") (pinfunction "12_GPIO18_12") (pintype "bidirectional"))
    )
    (net (code "89") (name "unconnected-(X3-13_GPIO27-Pad13)") (class "Default")
      (node (ref "X3") (pin "13") (pinfunction "13_GPIO27_13") (pintype "bidirectional"))
    )
    (net (code "90") (name "unconnected-(X3-15_GPIO22-Pad15)") (class "Default")
      (node (ref "X3") (pin "15") (pinfunction "15_GPIO22_15") (pintype "bidirectional"))
    )
    (net (code "91") (name "unconnected-(X3-16_GPIO23-Pad16)") (class "Default")
      (node (ref "X3") (pin "16") (pinfunction "16_GPIO23_16") (pintype "bidirectional"))
    )
    (net (code "92") (name "unconnected-(X3-17_+3V3-Pad17)") (class "Default")
      (node (ref "X3") (pin "17") (pinfunction "17_+3V3_17") (pintype "bidirectional"))
    )
    (net (code "93") (name "unconnected-(X3-18_GPIO24-Pad18)") (class "Default")
      (node (ref "X3") (pin "18") (pinfunction "18_GPIO24_18") (pintype "bidirectional"))
    )
    (net (code "94") (name "unconnected-(X3-22_GPIO25-Pad22)") (class "Default")
      (node (ref "X3") (pin "22") (pinfunction "22_GPIO25_22") (pintype "bidirectional"))
    )
    (net (code "95") (name "unconnected-(X3-26_CE1-GPIO7-Pad26)") (class "Default")
      (node (ref "X3") (pin "26") (pinfunction "26_CE1-GPIO7_26") (pintype "bidirectional"))
    )
  )
)
